# connection-schema.net
KiCad netlist of a schematic drawn in EAGLE
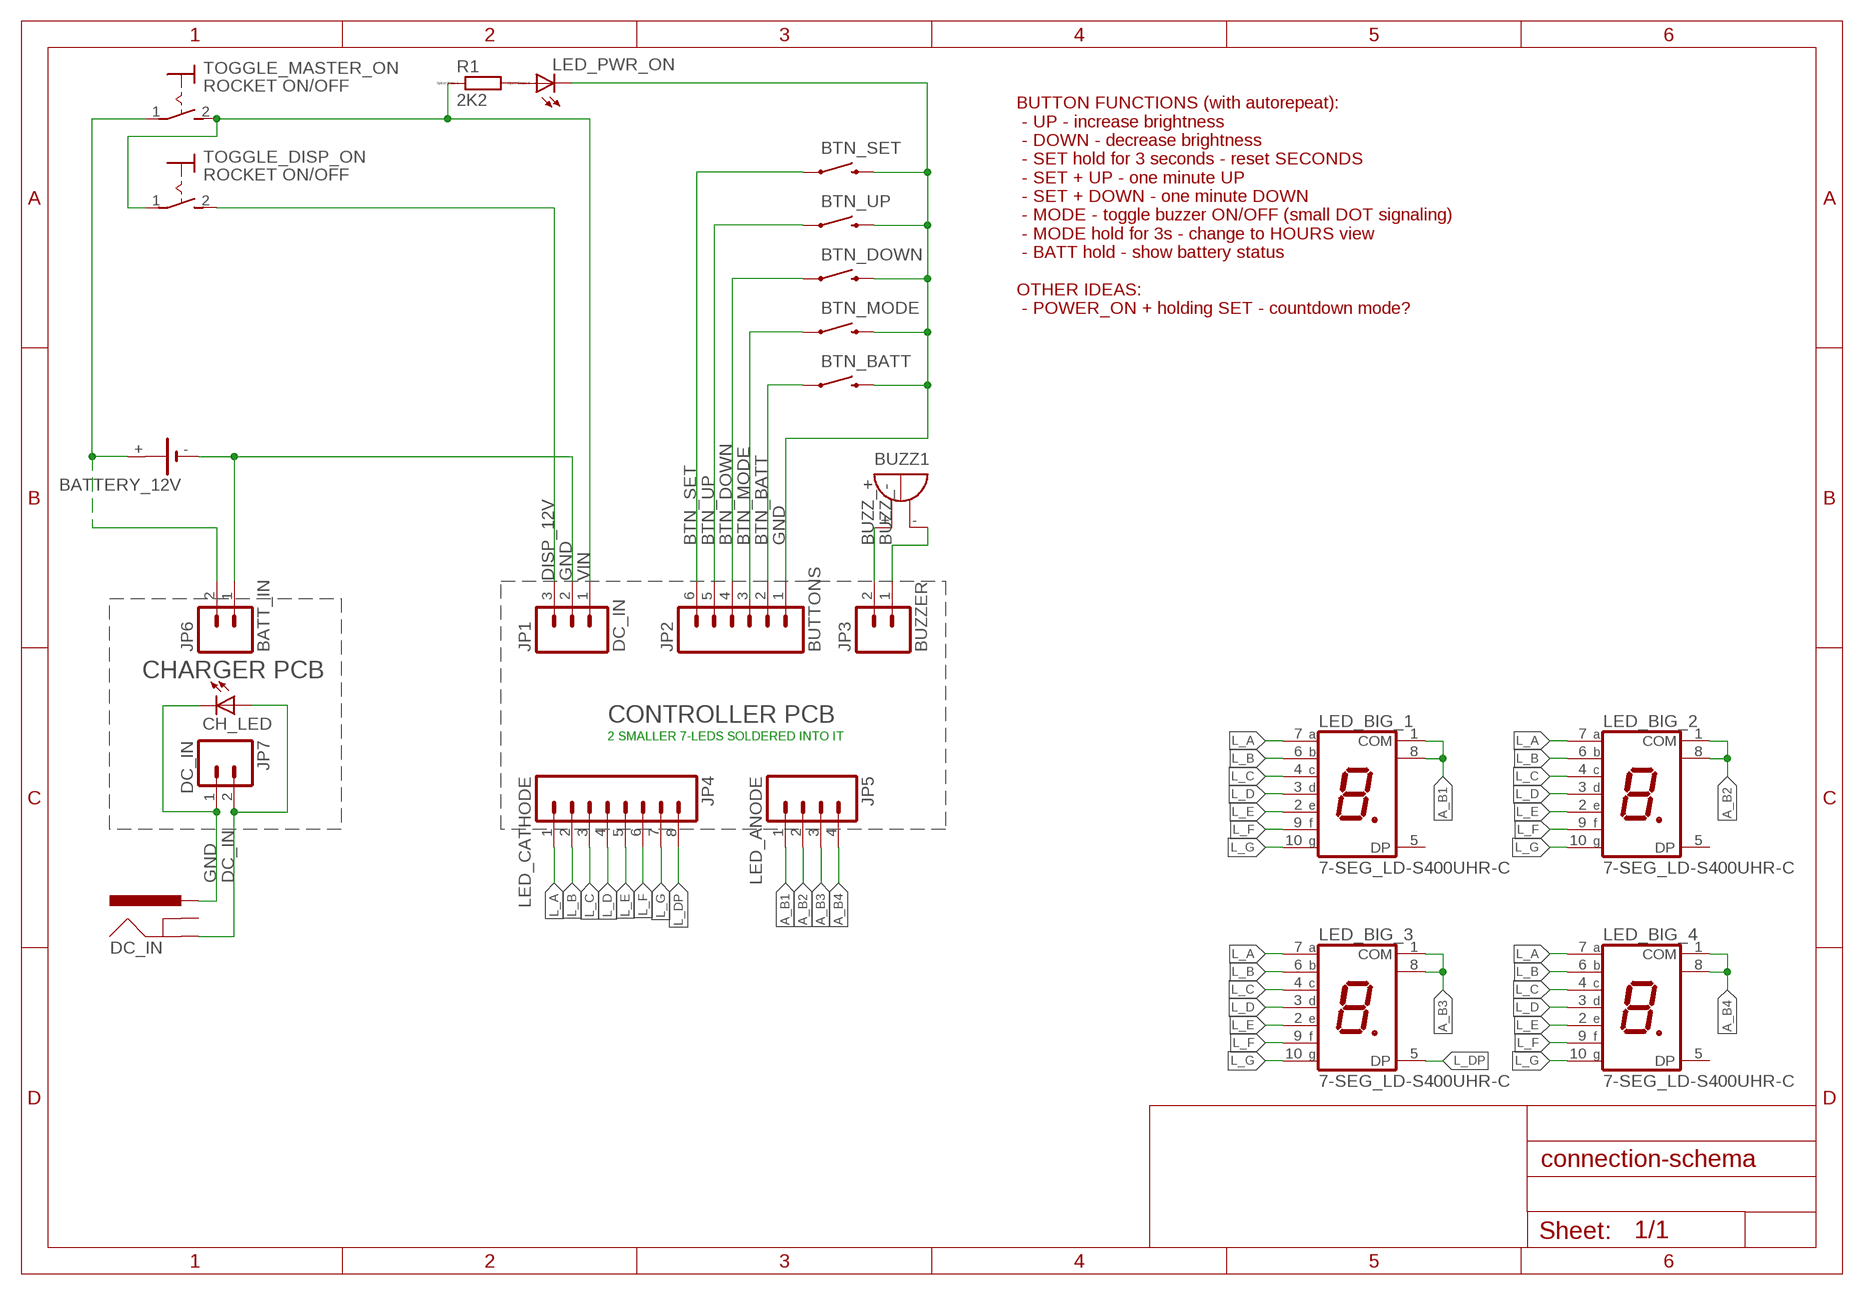
[diagram p0: schematic, sheet 1]

(export (version "E")
  (design (tool "Eeschema 10.0.6"))
  (components
    (comp (ref "BATTERY_12V")
      (value "12V 7Ah")
      (footprint "eagle-import:1V60R")
      (libsource (lib "eagle-import") (part "1V60R"))
    )
    (comp (ref "BTN_BATT")
      (value "SWITCH-MOMENTARY-2PTH")
      (footprint "eagle-import:TACTILE-PTH")
      (libsource (lib "eagle-import") (part "SWITCH-MOMENTARY-2PTH"))
    )
    (comp (ref "BTN_DOWN")
      (value "SWITCH-MOMENTARY-2PTH")
      (footprint "eagle-import:TACTILE-PTH")
      (libsource (lib "eagle-import") (part "SWITCH-MOMENTARY-2PTH"))
    )
    (comp (ref "BTN_MODE")
      (value "SWITCH-MOMENTARY-2PTH")
      (footprint "eagle-import:TACTILE-PTH")
      (libsource (lib "eagle-import") (part "SWITCH-MOMENTARY-2PTH"))
    )
    (comp (ref "BTN_SET")
      (value "SWITCH-MOMENTARY-2PTH")
      (footprint "eagle-import:TACTILE-PTH")
      (libsource (lib "eagle-import") (part "SWITCH-MOMENTARY-2PTH"))
    )
    (comp (ref "BTN_UP")
      (value "SWITCH-MOMENTARY-2PTH")
      (footprint "eagle-import:TACTILE-PTH")
      (libsource (lib "eagle-import") (part "SWITCH-MOMENTARY-2PTH"))
    )
    (comp (ref "BUZZ1")
      (value "F/BC40")
      (footprint "eagle-import:F_BC40")
      (libsource (lib "eagle-import") (part "F/BC40"))
    )
    (comp (ref "CH_LED")
      (value "LED5MM")
      (footprint "eagle-import:LED5MM")
      (libsource (lib "eagle-import") (part "LED5MM"))
    )
    (comp (ref "DC_IN")
      (value "POWER_JACKPTH")
      (footprint "eagle-import:POWER_JACK_PTH")
      (libsource (lib "eagle-import") (part "POWER_JACKPTH"))
    )
    (comp (ref "JP1")
      (value "DC_IN")
      (footprint "eagle-import:JST-3-PTH")
      (libsource (lib "eagle-import") (part "M03JST-PTH"))
    )
    (comp (ref "JP2")
      (value "BUTTONS")
      (footprint "eagle-import:1X06_LONGPADS")
      (libsource (lib "eagle-import") (part "M06LONGPADS"))
    )
    (comp (ref "JP3")
      (value "BUZZER")
      (footprint "eagle-import:MOLEX-1X2")
      (libsource (lib "eagle-import") (part "M02POLAR"))
    )
    (comp (ref "JP4")
      (value "LED_CATHODE")
      (footprint "eagle-import:1X08_ROUND")
      (libsource (lib "eagle-import") (part "M08"))
    )
    (comp (ref "JP5")
      (value "LED_ANODE")
      (footprint "eagle-import:1X04")
      (libsource (lib "eagle-import") (part "M04PTH"))
    )
    (comp (ref "JP6")
      (value "BATT_IN")
      (footprint "eagle-import:MOLEX-1X2")
      (libsource (lib "eagle-import") (part "M02POLAR"))
    )
    (comp (ref "JP7")
      (value "DC_IN")
      (footprint "eagle-import:MOLEX-1X2")
      (libsource (lib "eagle-import") (part "M02POLAR"))
    )
    (comp (ref "LED_BIG_1")
      (value "7-SEG_LD-S400UHR-C")
      (footprint "eagle-import:LD-S400UHR-C")
      (libsource (lib "eagle-import") (part "7-SEG_LD-S400UHR-C"))
    )
    (comp (ref "LED_BIG_2")
      (value "7-SEG_LD-S400UHR-C")
      (footprint "eagle-import:LD-S400UHR-C")
      (libsource (lib "eagle-import") (part "7-SEG_LD-S400UHR-C"))
    )
    (comp (ref "LED_BIG_3")
      (value "7-SEG_LD-S400UHR-C")
      (footprint "eagle-import:LD-S400UHR-C")
      (libsource (lib "eagle-import") (part "7-SEG_LD-S400UHR-C"))
    )
    (comp (ref "LED_BIG_4")
      (value "7-SEG_LD-S400UHR-C")
      (footprint "eagle-import:LD-S400UHR-C")
      (libsource (lib "eagle-import") (part "7-SEG_LD-S400UHR-C"))
    )
    (comp (ref "LED_PWR_ON")
      (value "LED5MM")
      (footprint "eagle-import:LED5MM")
      (libsource (lib "eagle-import") (part "LED5MM"))
    )
    (comp (ref "R1")
      (value "2K2")
      (footprint "eagle-import:0207_10")
      (libsource (lib "eagle-import") (part "R-EU_0207_10"))
    )
    (comp (ref "TOGGLE_DISP_ON")
      (value "ROCKET ON/OFF")
      (footprint "eagle-import:MS243")
      (libsource (lib "eagle-import") (part "MS243"))
    )
    (comp (ref "TOGGLE_MASTER_ON")
      (value "ROCKET ON/OFF")
      (footprint "eagle-import:MS243")
      (libsource (lib "eagle-import") (part "MS243"))
    )
  )
  (nets
    (net (code "1") (name "/BTN_BATT") (class "Default")
      (node (ref "BTN_BATT") (pin "1") (pinfunction "1_1") (pintype "passive"))
      (node (ref "JP2") (pin "2") (pinfunction "2_2") (pintype "passive"))
    )
    (net (code "2") (name "/BTN_DOWN") (class "Default")
      (node (ref "BTN_DOWN") (pin "1") (pinfunction "1_1") (pintype "passive"))
      (node (ref "JP2") (pin "4") (pinfunction "4_4") (pintype "passive"))
    )
    (net (code "3") (name "/BTN_MODE") (class "Default")
      (node (ref "BTN_MODE") (pin "1") (pinfunction "1_1") (pintype "passive"))
    )
    (net (code "4") (name "/BTN_SET") (class "Default")
      (node (ref "BTN_SET") (pin "1") (pinfunction "1_1") (pintype "passive"))
      (node (ref "JP2") (pin "6") (pinfunction "6_6") (pintype "passive"))
    )
    (net (code "5") (name "/BTN_UP") (class "Default")
      (node (ref "BTN_UP") (pin "1") (pinfunction "1_1") (pintype "passive"))
      (node (ref "JP2") (pin "5") (pinfunction "5_5") (pintype "passive"))
    )
    (net (code "6") (name "/BUZZ_+") (class "Default")
      (node (ref "BUZZ1") (pin "+") (pinfunction "+_+") (pintype "passive"))
      (node (ref "JP3") (pin "2") (pinfunction "2_2") (pintype "passive"))
    )
    (net (code "7") (name "/BUZZ_-") (class "Default")
      (node (ref "BUZZ1") (pin "-") (pinfunction "-_-") (pintype "passive"))
      (node (ref "JP3") (pin "1") (pinfunction "1_1") (pintype "passive"))
    )
    (net (code "8") (name "/DC_IN") (class "Default")
      (node (ref "CH_LED") (pin "A") (pinfunction "A_A") (pintype "passive"))
      (node (ref "DC_IN") (pin "GND") (pinfunction "GND_GND") (pintype "bidirectional"))
      (node (ref "JP7") (pin "2") (pinfunction "2_2") (pintype "passive"))
    )
    (net (code "9") (name "/DISP_12V") (class "Default")
      (node (ref "JP1") (pin "3") (pinfunction "3_3") (pintype "passive"))
      (node (ref "TOGGLE_DISP_ON") (pin "2") (pinfunction "S_2") (pintype "passive"))
    )
    (net (code "10") (name "/GND") (class "Default")
      (node (ref "BATTERY_12V") (pin "-") (pinfunction "-_-") (pintype "passive"))
      (node (ref "BTN_BATT") (pin "3") (pinfunction "2_3") (pintype "passive"))
      (node (ref "BTN_DOWN") (pin "3") (pinfunction "2_3") (pintype "passive"))
      (node (ref "BTN_MODE") (pin "3") (pinfunction "2_3") (pintype "passive"))
      (node (ref "BTN_SET") (pin "3") (pinfunction "2_3") (pintype "passive"))
      (node (ref "BTN_UP") (pin "3") (pinfunction "2_3") (pintype "passive"))
      (node (ref "CH_LED") (pin "K") (pinfunction "C_K") (pintype "passive"))
      (node (ref "DC_IN") (pin "PWR") (pinfunction "PWR_PWR") (pintype "bidirectional"))
      (node (ref "JP1") (pin "2") (pinfunction "2_2") (pintype "passive"))
      (node (ref "JP2") (pin "1") (pinfunction "1_1") (pintype "passive"))
      (node (ref "JP6") (pin "1") (pinfunction "1_1") (pintype "passive"))
      (node (ref "JP7") (pin "1") (pinfunction "1_1") (pintype "passive"))
      (node (ref "LED_PWR_ON") (pin "K") (pinfunction "C_K") (pintype "passive"))
    )
    (net (code "11") (name "/VIN") (class "Default")
      (node (ref "JP1") (pin "1") (pinfunction "1_1") (pintype "passive"))
      (node (ref "R1") (pin "1") (pinfunction "1_1") (pintype "passive"))
      (node (ref "TOGGLE_DISP_ON") (pin "1") (pinfunction "P_1") (pintype "passive"))
      (node (ref "TOGGLE_MASTER_ON") (pin "2") (pinfunction "S_2") (pintype "passive"))
    )
    (net (code "12") (name "A_B1") (class "Default")
      (node (ref "JP5") (pin "1") (pinfunction "1_1") (pintype "passive"))
      (node (ref "LED_BIG_1") (pin "1") (pinfunction "COM_1") (pintype "passive"))
      (node (ref "LED_BIG_1") (pin "8") (pinfunction "COM_8") (pintype "passive"))
    )
    (net (code "13") (name "A_B2") (class "Default")
      (node (ref "JP5") (pin "2") (pinfunction "2_2") (pintype "passive"))
      (node (ref "LED_BIG_2") (pin "1") (pinfunction "COM_1") (pintype "passive"))
      (node (ref "LED_BIG_2") (pin "8") (pinfunction "COM_8") (pintype "passive"))
    )
    (net (code "14") (name "A_B3") (class "Default")
      (node (ref "JP5") (pin "3") (pinfunction "3_3") (pintype "passive"))
      (node (ref "LED_BIG_3") (pin "1") (pinfunction "COM_1") (pintype "passive"))
      (node (ref "LED_BIG_3") (pin "8") (pinfunction "COM_8") (pintype "passive"))
    )
    (net (code "15") (name "A_B4") (class "Default")
      (node (ref "JP5") (pin "4") (pinfunction "4_4") (pintype "passive"))
      (node (ref "LED_BIG_4") (pin "1") (pinfunction "COM_1") (pintype "passive"))
      (node (ref "LED_BIG_4") (pin "8") (pinfunction "COM_8") (pintype "passive"))
    )
    (net (code "16") (name "L_A") (class "Default")
      (node (ref "JP4") (pin "1") (pinfunction "1_1") (pintype "passive"))
      (node (ref "LED_BIG_1") (pin "7") (pinfunction "A_7") (pintype "passive"))
      (node (ref "LED_BIG_2") (pin "7") (pinfunction "A_7") (pintype "passive"))
      (node (ref "LED_BIG_3") (pin "7") (pinfunction "A_7") (pintype "passive"))
      (node (ref "LED_BIG_4") (pin "7") (pinfunction "A_7") (pintype "passive"))
    )
    (net (code "17") (name "L_B") (class "Default")
      (node (ref "JP4") (pin "2") (pinfunction "2_2") (pintype "passive"))
      (node (ref "LED_BIG_1") (pin "6") (pinfunction "B_6") (pintype "passive"))
      (node (ref "LED_BIG_2") (pin "6") (pinfunction "B_6") (pintype "passive"))
      (node (ref "LED_BIG_3") (pin "6") (pinfunction "B_6") (pintype "passive"))
      (node (ref "LED_BIG_4") (pin "6") (pinfunction "B_6") (pintype "passive"))
    )
    (net (code "18") (name "L_C") (class "Default")
      (node (ref "JP4") (pin "3") (pinfunction "3_3") (pintype "passive"))
      (node (ref "LED_BIG_1") (pin "4") (pinfunction "C_4") (pintype "passive"))
      (node (ref "LED_BIG_2") (pin "4") (pinfunction "C_4") (pintype "passive"))
      (node (ref "LED_BIG_3") (pin "4") (pinfunction "C_4") (pintype "passive"))
      (node (ref "LED_BIG_4") (pin "4") (pinfunction "C_4") (pintype "passive"))
    )
    (net (code "19") (name "L_D") (class "Default")
      (node (ref "JP4") (pin "4") (pinfunction "4_4") (pintype "passive"))
      (node (ref "LED_BIG_1") (pin "3") (pinfunction "D_3") (pintype "passive"))
      (node (ref "LED_BIG_2") (pin "3") (pinfunction "D_3") (pintype "passive"))
      (node (ref "LED_BIG_3") (pin "3") (pinfunction "D_3") (pintype "passive"))
      (node (ref "LED_BIG_4") (pin "3") (pinfunction "D_3") (pintype "passive"))
    )
    (net (code "20") (name "L_DP") (class "Default")
      (node (ref "JP4") (pin "8") (pinfunction "8_8") (pintype "passive"))
      (node (ref "LED_BIG_3") (pin "5") (pinfunction "DP_5") (pintype "passive"))
    )
    (net (code "21") (name "L_E") (class "Default")
      (node (ref "JP4") (pin "5") (pinfunction "5_5") (pintype "passive"))
      (node (ref "LED_BIG_1") (pin "2") (pinfunction "E_2") (pintype "passive"))
      (node (ref "LED_BIG_2") (pin "2") (pinfunction "E_2") (pintype "passive"))
      (node (ref "LED_BIG_3") (pin "2") (pinfunction "E_2") (pintype "passive"))
      (node (ref "LED_BIG_4") (pin "2") (pinfunction "E_2") (pintype "passive"))
    )
    (net (code "22") (name "L_F") (class "Default")
      (node (ref "JP4") (pin "6") (pinfunction "6_6") (pintype "passive"))
      (node (ref "LED_BIG_1") (pin "9") (pinfunction "F_9") (pintype "passive"))
      (node (ref "LED_BIG_2") (pin "9") (pinfunction "F_9") (pintype "passive"))
      (node (ref "LED_BIG_3") (pin "9") (pinfunction "F_9") (pintype "passive"))
      (node (ref "LED_BIG_4") (pin "9") (pinfunction "F_9") (pintype "passive"))
    )
    (net (code "23") (name "L_G") (class "Default")
      (node (ref "JP4") (pin "7") (pinfunction "7_7") (pintype "passive"))
      (node (ref "LED_BIG_1") (pin "10") (pinfunction "G_10") (pintype "passive"))
      (node (ref "LED_BIG_2") (pin "10") (pinfunction "G_10") (pintype "passive"))
      (node (ref "LED_BIG_3") (pin "10") (pinfunction "G_10") (pintype "passive"))
      (node (ref "LED_BIG_4") (pin "10") (pinfunction "G_10") (pintype "passive"))
    )
    (net (code "24") (name "Net-(LED_PWR_ON-PadA)") (class "Default")
      (node (ref "LED_PWR_ON") (pin "A") (pinfunction "A_A") (pintype "passive"))
      (node (ref "R1") (pin "2") (pinfunction "2_2") (pintype "passive"))
    )
    (net (code "25") (name "Net-(TOGGLE_MASTER_ON-P)") (class "Default")
      (node (ref "BATTERY_12V") (pin "+") (pinfunction "+_+") (pintype "passive"))
      (node (ref "JP6") (pin "2") (pinfunction "2_2") (pintype "passive"))
      (node (ref "TOGGLE_MASTER_ON") (pin "1") (pinfunction "P_1") (pintype "passive"))
    )
    (net (code "26") (name "unconnected-(BATTERY_12V-+-Pad+@1)") (class "Default")
      (node (ref "BATTERY_12V") (pin "+@1") (pinfunction "+_+@1") (pintype "passive"))
    )
    (net (code "27") (name "unconnected-(DC_IN-PadGNDBREAK)") (class "Default")
      (node (ref "DC_IN") (pin "GNDBREAK") (pinfunction "GNDBREAK_GNDBREAK") (pintype "bidirectional"))
    )
    (net (code "28") (name "unconnected-(JP2-Pad3)") (class "Default")
      (node (ref "JP2") (pin "3") (pinfunction "3_3") (pintype "passive"))
    )
    (net (code "29") (name "unconnected-(LED_BIG_1-DP-Pad5)") (class "Default")
      (node (ref "LED_BIG_1") (pin "5") (pinfunction "DP_5") (pintype "passive"))
    )
    (net (code "30") (name "unconnected-(LED_BIG_2-DP-Pad5)") (class "Default")
      (node (ref "LED_BIG_2") (pin "5") (pinfunction "DP_5") (pintype "passive"))
    )
    (net (code "31") (name "unconnected-(LED_BIG_4-DP-Pad5)") (class "Default")
      (node (ref "LED_BIG_4") (pin "5") (pinfunction "DP_5") (pintype "passive"))
    )
  )
)
